# MCH_FPGA_Bank_47_48_67_HP_VHDCI.net
KiCad netlist of a schematic drawn in Altium Designer
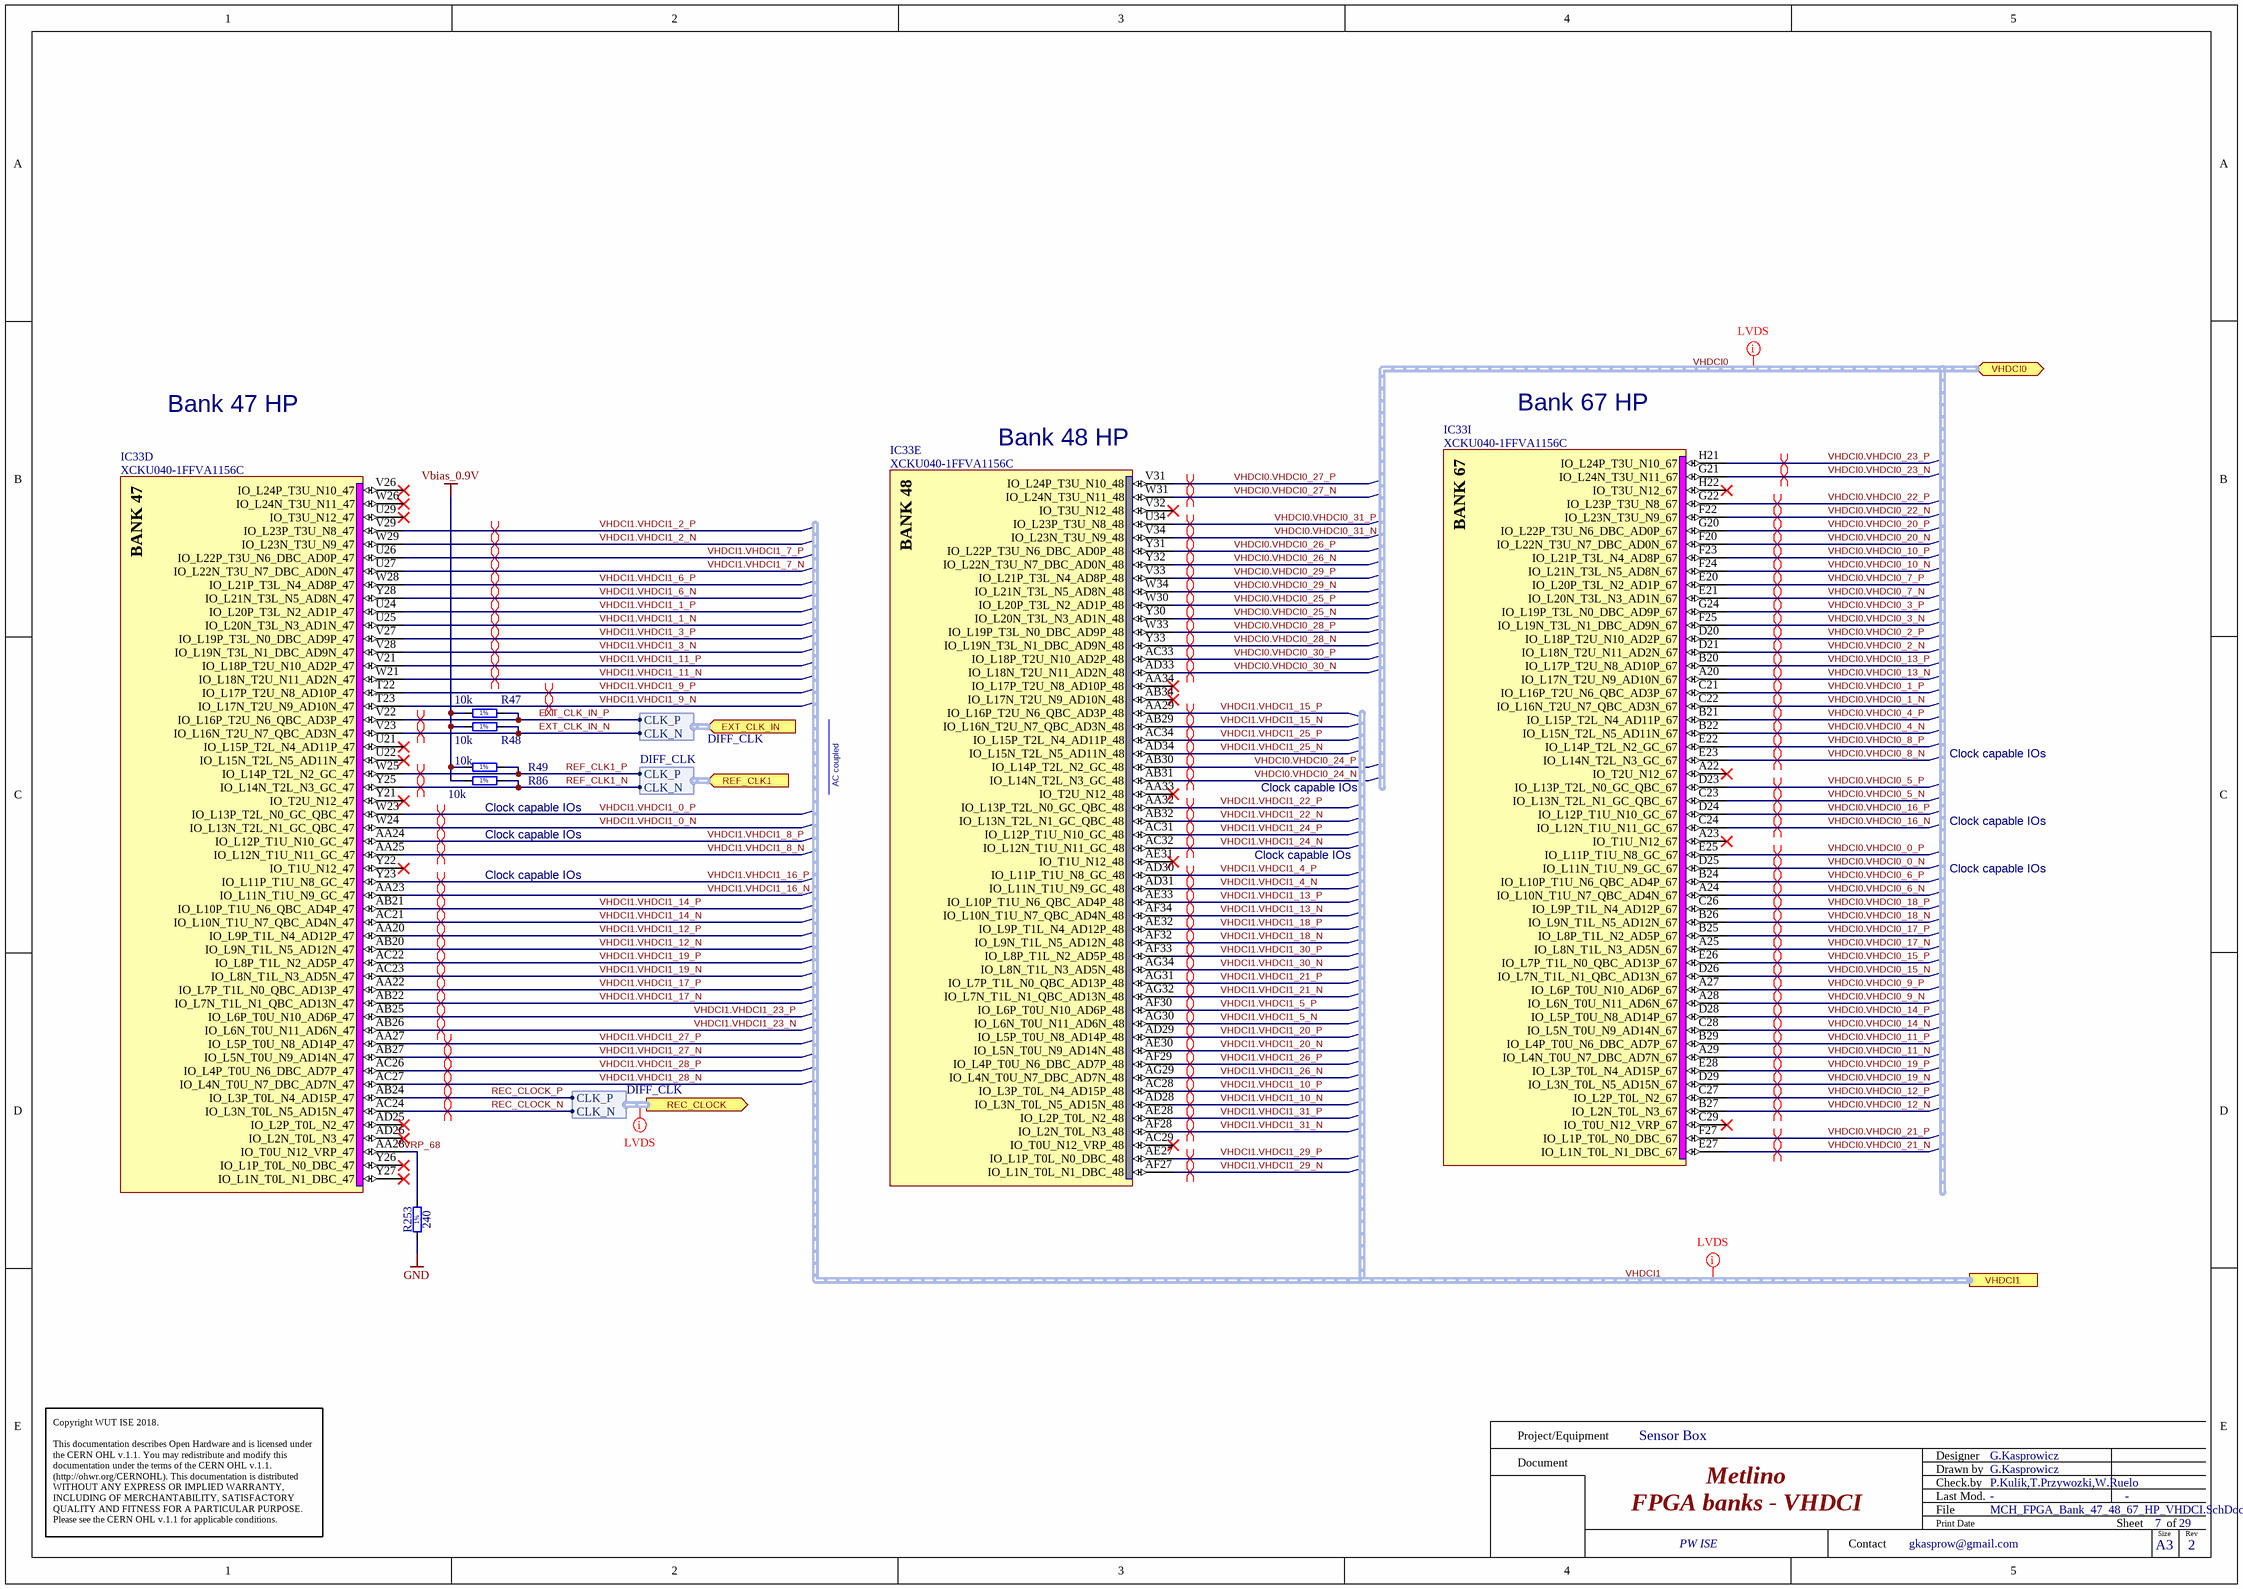
[diagram p0: MCH_FPGA_Bank_47_48_67_HP_VHDCI.SchDoc]

(export (version "E")
  (design (tool "Eeschema 10.0.6"))
  (components
    (comp (ref "IC33")
      (value "XCKU040-1FFVA1156C")
      (footprint "BGA1156C100P34X34_3500X3500X350")
      (description "Kintex UltraScale FPGA, 520 I/O, 530K Cells, 1156-Ball BGA, Speed Grade 1, Commercial Grade")
      (fields (field (name "MANUFACTURER") "XILINX") (field (name "AUTHOR") "CERN DEM CA"))
      (libsource (lib "ICs And Semiconductors") (part "XCKU040-1FFVA1156C"))
    )
    (comp (ref "R47")
      (value "10k")
      (footprint "RESC1005X40N")
      (description "Resistor - 1%")
      (fields
        (field (name "MANUFACTURER PART NUMBER") "R0402_10K_1%_0.0625W_100PPM")
        (field (name "MANUFACTURER") "GENERIC")
        (field (name "AUTHOR") "CERN DEM JLC")
      )
      (libsource (lib "Resistors") (part "Resistor - 1%"))
    )
    (comp (ref "R48")
      (value "10k")
      (footprint "RESC1005X40N")
      (description "Resistor - 1%")
      (fields
        (field (name "MANUFACTURER PART NUMBER") "R0402_10K_1%_0.0625W_100PPM")
        (field (name "MANUFACTURER") "GENERIC")
        (field (name "AUTHOR") "CERN DEM JLC")
      )
      (libsource (lib "Resistors") (part "Resistor - 1%"))
    )
    (comp (ref "R49")
      (value "10k")
      (footprint "RESC1005X40N")
      (description "Resistor - 1%")
      (fields
        (field (name "MANUFACTURER PART NUMBER") "R0402_10K_1%_0.0625W_100PPM")
        (field (name "MANUFACTURER") "GENERIC")
        (field (name "AUTHOR") "CERN DEM JLC")
      )
      (libsource (lib "Resistors") (part "Resistor - 1%"))
    )
    (comp (ref "R86")
      (value "10k")
      (footprint "RESC1005X40N")
      (description "Resistor - 1%")
      (fields
        (field (name "MANUFACTURER PART NUMBER") "R0402_10K_1%_0.0625W_100PPM")
        (field (name "MANUFACTURER") "GENERIC")
        (field (name "AUTHOR") "CERN DEM JLC")
      )
      (libsource (lib "Resistors") (part "Resistor - 1%"))
    )
    (comp (ref "R253")
      (value "240")
      (footprint "RESC1005X40N")
      (description "Resistor - 1%")
      (fields
        (field (name "MANUFACTURER PART NUMBER") "R0402_240R_1%_0.0625W_100PPM")
        (field (name "MANUFACTURER") "GENERIC")
        (field (name "AUTHOR") "CERN DEM JLC")
      )
      (libsource (lib "Resistors") (part "Resistor - 1%"))
    )
  )
  (nets
    (net (code "4") (name "/EXT_CLK_IN_N") (class "Default")
      (node (ref "IC33") (pin "V23") (pinfunction "IO_L16N_T2U_N7_QBC_AD3N_47_V23") (pintype "bidirectional"))
      (node (ref "R48") (pin "2") (pinfunction "2_2") (pintype "passive"))
    )
    (net (code "5") (name "/EXT_CLK_IN_P") (class "Default")
      (node (ref "IC33") (pin "V22") (pinfunction "IO_L16P_T2U_N6_QBC_AD3P_47_V22") (pintype "bidirectional"))
      (node (ref "R47") (pin "2") (pinfunction "2_2") (pintype "passive"))
    )
    (net (code "6") (name "/REC_CLOCK_N") (class "Default")
      (node (ref "IC33") (pin "AC24") (pinfunction "IO_L3N_T0L_N5_AD15N_47_AC24") (pintype "bidirectional"))
    )
    (net (code "7") (name "/REC_CLOCK_P") (class "Default")
      (node (ref "IC33") (pin "AB24") (pinfunction "IO_L3P_T0L_N4_AD15P_47_AB24") (pintype "bidirectional"))
    )
    (net (code "8") (name "/REF_CLK1_N") (class "Default")
      (node (ref "IC33") (pin "Y25") (pinfunction "IO_L14N_T2L_N3_GC_47_Y25") (pintype "bidirectional"))
      (node (ref "R86") (pin "2") (pinfunction "2_2") (pintype "passive"))
    )
    (net (code "9") (name "/REF_CLK1_P") (class "Default")
      (node (ref "IC33") (pin "W25") (pinfunction "IO_L14P_T2L_N2_GC_47_W25") (pintype "bidirectional"))
      (node (ref "R49") (pin "2") (pinfunction "2_2") (pintype "passive"))
    )
    (net (code "10") (name "/VHDCI0.VHDCI0_0_N") (class "Default")
      (node (ref "IC33") (pin "D25") (pinfunction "IO_L11N_T1U_N9_GC_67_D25") (pintype "bidirectional"))
    )
    (net (code "11") (name "/VHDCI0.VHDCI0_0_P") (class "Default")
      (node (ref "IC33") (pin "E25") (pinfunction "IO_L11P_T1U_N8_GC_67_E25") (pintype "bidirectional"))
    )
    (net (code "12") (name "/VHDCI0.VHDCI0_1_N") (class "Default")
      (node (ref "IC33") (pin "C22") (pinfunction "IO_L16N_T2U_N7_QBC_AD3N_67_C22") (pintype "bidirectional"))
    )
    (net (code "13") (name "/VHDCI0.VHDCI0_1_P") (class "Default")
      (node (ref "IC33") (pin "C21") (pinfunction "IO_L16P_T2U_N6_QBC_AD3P_67_C21") (pintype "bidirectional"))
    )
    (net (code "14") (name "/VHDCI0.VHDCI0_2_N") (class "Default")
      (node (ref "IC33") (pin "D21") (pinfunction "IO_L18N_T2U_N11_AD2N_67_D21") (pintype "bidirectional"))
    )
    (net (code "15") (name "/VHDCI0.VHDCI0_2_P") (class "Default")
      (node (ref "IC33") (pin "D20") (pinfunction "IO_L18P_T2U_N10_AD2P_67_D20") (pintype "bidirectional"))
    )
    (net (code "16") (name "/VHDCI0.VHDCI0_3_N") (class "Default")
      (node (ref "IC33") (pin "F25") (pinfunction "IO_L19N_T3L_N1_DBC_AD9N_67_F25") (pintype "bidirectional"))
    )
    (net (code "17") (name "/VHDCI0.VHDCI0_3_P") (class "Default")
      (node (ref "IC33") (pin "G24") (pinfunction "IO_L19P_T3L_N0_DBC_AD9P_67_G24") (pintype "bidirectional"))
    )
    (net (code "18") (name "/VHDCI0.VHDCI0_4_N") (class "Default")
      (node (ref "IC33") (pin "B22") (pinfunction "IO_L15N_T2L_N5_AD11N_67_B22") (pintype "bidirectional"))
    )
    (net (code "19") (name "/VHDCI0.VHDCI0_4_P") (class "Default")
      (node (ref "IC33") (pin "B21") (pinfunction "IO_L15P_T2L_N4_AD11P_67_B21") (pintype "bidirectional"))
    )
    (net (code "20") (name "/VHDCI0.VHDCI0_5_N") (class "Default")
      (node (ref "IC33") (pin "C23") (pinfunction "IO_L13N_T2L_N1_GC_QBC_67_C23") (pintype "bidirectional"))
    )
    (net (code "21") (name "/VHDCI0.VHDCI0_5_P") (class "Default")
      (node (ref "IC33") (pin "D23") (pinfunction "IO_L13P_T2L_N0_GC_QBC_67_D23") (pintype "bidirectional"))
    )
    (net (code "22") (name "/VHDCI0.VHDCI0_6_N") (class "Default")
      (node (ref "IC33") (pin "A24") (pinfunction "IO_L10N_T1U_N7_QBC_AD4N_67_A24") (pintype "bidirectional"))
    )
    (net (code "23") (name "/VHDCI0.VHDCI0_6_P") (class "Default")
      (node (ref "IC33") (pin "B24") (pinfunction "IO_L10P_T1U_N6_QBC_AD4P_67_B24") (pintype "bidirectional"))
    )
    (net (code "24") (name "/VHDCI0.VHDCI0_7_N") (class "Default")
      (node (ref "IC33") (pin "E21") (pinfunction "IO_L20N_T3L_N3_AD1N_67_E21") (pintype "bidirectional"))
    )
    (net (code "25") (name "/VHDCI0.VHDCI0_7_P") (class "Default")
      (node (ref "IC33") (pin "E20") (pinfunction "IO_L20P_T3L_N2_AD1P_67_E20") (pintype "bidirectional"))
    )
    (net (code "26") (name "/VHDCI0.VHDCI0_8_N") (class "Default")
      (node (ref "IC33") (pin "E23") (pinfunction "IO_L14N_T2L_N3_GC_67_E23") (pintype "bidirectional"))
    )
    (net (code "27") (name "/VHDCI0.VHDCI0_8_P") (class "Default")
      (node (ref "IC33") (pin "E22") (pinfunction "IO_L14P_T2L_N2_GC_67_E22") (pintype "bidirectional"))
    )
    (net (code "28") (name "/VHDCI0.VHDCI0_9_N") (class "Default")
      (node (ref "IC33") (pin "A28") (pinfunction "IO_L6N_T0U_N11_AD6N_67_A28") (pintype "bidirectional"))
    )
    (net (code "29") (name "/VHDCI0.VHDCI0_9_P") (class "Default")
      (node (ref "IC33") (pin "A27") (pinfunction "IO_L6P_T0U_N10_AD6P_67_A27") (pintype "bidirectional"))
    )
    (net (code "30") (name "/VHDCI0.VHDCI0_10_N") (class "Default")
      (node (ref "IC33") (pin "F24") (pinfunction "IO_L21N_T3L_N5_AD8N_67_F24") (pintype "bidirectional"))
    )
    (net (code "31") (name "/VHDCI0.VHDCI0_10_P") (class "Default")
      (node (ref "IC33") (pin "F23") (pinfunction "IO_L21P_T3L_N4_AD8P_67_F23") (pintype "bidirectional"))
    )
    (net (code "32") (name "/VHDCI0.VHDCI0_11_N") (class "Default")
      (node (ref "IC33") (pin "A29") (pinfunction "IO_L4N_T0U_N7_DBC_AD7N_67_A29") (pintype "bidirectional"))
    )
    (net (code "33") (name "/VHDCI0.VHDCI0_11_P") (class "Default")
      (node (ref "IC33") (pin "B29") (pinfunction "IO_L4P_T0U_N6_DBC_AD7P_67_B29") (pintype "bidirectional"))
    )
    (net (code "34") (name "/VHDCI0.VHDCI0_12_N") (class "Default")
      (node (ref "IC33") (pin "B27") (pinfunction "IO_L2N_T0L_N3_67_B27") (pintype "bidirectional"))
    )
    (net (code "35") (name "/VHDCI0.VHDCI0_12_P") (class "Default")
      (node (ref "IC33") (pin "C27") (pinfunction "IO_L2P_T0L_N2_67_C27") (pintype "bidirectional"))
    )
    (net (code "36") (name "/VHDCI0.VHDCI0_13_N") (class "Default")
      (node (ref "IC33") (pin "A20") (pinfunction "IO_L17N_T2U_N9_AD10N_67_A20") (pintype "bidirectional"))
    )
    (net (code "37") (name "/VHDCI0.VHDCI0_13_P") (class "Default")
      (node (ref "IC33") (pin "B20") (pinfunction "IO_L17P_T2U_N8_AD10P_67_B20") (pintype "bidirectional"))
    )
    (net (code "38") (name "/VHDCI0.VHDCI0_14_N") (class "Default")
      (node (ref "IC33") (pin "C28") (pinfunction "IO_L5N_T0U_N9_AD14N_67_C28") (pintype "bidirectional"))
    )
    (net (code "39") (name "/VHDCI0.VHDCI0_14_P") (class "Default")
      (node (ref "IC33") (pin "D28") (pinfunction "IO_L5P_T0U_N8_AD14P_67_D28") (pintype "bidirectional"))
    )
    (net (code "40") (name "/VHDCI0.VHDCI0_15_N") (class "Default")
      (node (ref "IC33") (pin "D26") (pinfunction "IO_L7N_T1L_N1_QBC_AD13N_67_D26") (pintype "bidirectional"))
    )
    (net (code "41") (name "/VHDCI0.VHDCI0_15_P") (class "Default")
      (node (ref "IC33") (pin "E26") (pinfunction "IO_L7P_T1L_N0_QBC_AD13P_67_E26") (pintype "bidirectional"))
    )
    (net (code "42") (name "/VHDCI0.VHDCI0_16_N") (class "Default")
      (node (ref "IC33") (pin "C24") (pinfunction "IO_L12N_T1U_N11_GC_67_C24") (pintype "bidirectional"))
    )
    (net (code "43") (name "/VHDCI0.VHDCI0_16_P") (class "Default")
      (node (ref "IC33") (pin "D24") (pinfunction "IO_L12P_T1U_N10_GC_67_D24") (pintype "bidirectional"))
    )
    (net (code "44") (name "/VHDCI0.VHDCI0_17_N") (class "Default")
      (node (ref "IC33") (pin "A25") (pinfunction "IO_L8N_T1L_N3_AD5N_67_A25") (pintype "bidirectional"))
    )
    (net (code "45") (name "/VHDCI0.VHDCI0_17_P") (class "Default")
      (node (ref "IC33") (pin "B25") (pinfunction "IO_L8P_T1L_N2_AD5P_67_B25") (pintype "bidirectional"))
    )
    (net (code "46") (name "/VHDCI0.VHDCI0_18_N") (class "Default")
      (node (ref "IC33") (pin "B26") (pinfunction "IO_L9N_T1L_N5_AD12N_67_B26") (pintype "bidirectional"))
    )
    (net (code "47") (name "/VHDCI0.VHDCI0_18_P") (class "Default")
      (node (ref "IC33") (pin "C26") (pinfunction "IO_L9P_T1L_N4_AD12P_67_C26") (pintype "bidirectional"))
    )
    (net (code "48") (name "/VHDCI0.VHDCI0_19_N") (class "Default")
      (node (ref "IC33") (pin "D29") (pinfunction "IO_L3N_T0L_N5_AD15N_67_D29") (pintype "bidirectional"))
    )
    (net (code "49") (name "/VHDCI0.VHDCI0_19_P") (class "Default")
      (node (ref "IC33") (pin "E28") (pinfunction "IO_L3P_T0L_N4_AD15P_67_E28") (pintype "bidirectional"))
    )
    (net (code "50") (name "/VHDCI0.VHDCI0_20_N") (class "Default")
      (node (ref "IC33") (pin "F20") (pinfunction "IO_L22N_T3U_N7_DBC_AD0N_67_F20") (pintype "bidirectional"))
    )
    (net (code "51") (name "/VHDCI0.VHDCI0_20_P") (class "Default")
      (node (ref "IC33") (pin "G20") (pinfunction "IO_L22P_T3U_N6_DBC_AD0P_67_G20") (pintype "bidirectional"))
    )
    (net (code "52") (name "/VHDCI0.VHDCI0_21_N") (class "Default")
      (node (ref "IC33") (pin "E27") (pinfunction "IO_L1N_T0L_N1_DBC_67_E27") (pintype "bidirectional"))
    )
    (net (code "53") (name "/VHDCI0.VHDCI0_21_P") (class "Default")
      (node (ref "IC33") (pin "F27") (pinfunction "IO_L1P_T0L_N0_DBC_67_F27") (pintype "bidirectional"))
    )
    (net (code "54") (name "/VHDCI0.VHDCI0_22_N") (class "Default")
      (node (ref "IC33") (pin "F22") (pinfunction "IO_L23N_T3U_N9_67_F22") (pintype "bidirectional"))
    )
    (net (code "55") (name "/VHDCI0.VHDCI0_22_P") (class "Default")
      (node (ref "IC33") (pin "G22") (pinfunction "IO_L23P_T3U_N8_67_G22") (pintype "bidirectional"))
    )
    (net (code "56") (name "/VHDCI0.VHDCI0_23_N") (class "Default")
      (node (ref "IC33") (pin "G21") (pinfunction "IO_L24N_T3U_N11_67_G21") (pintype "bidirectional"))
    )
    (net (code "57") (name "/VHDCI0.VHDCI0_23_P") (class "Default")
      (node (ref "IC33") (pin "H21") (pinfunction "IO_L24P_T3U_N10_67_H21") (pintype "bidirectional"))
    )
    (net (code "58") (name "/VHDCI0.VHDCI0_24_N") (class "Default")
      (node (ref "IC33") (pin "AB31") (pinfunction "IO_L14N_T2L_N3_GC_48_AB31") (pintype "bidirectional"))
    )
    (net (code "59") (name "/VHDCI0.VHDCI0_24_P") (class "Default")
      (node (ref "IC33") (pin "AB30") (pinfunction "IO_L14P_T2L_N2_GC_48_AB30") (pintype "bidirectional"))
    )
    (net (code "60") (name "/VHDCI0.VHDCI0_25_N") (class "Default")
      (node (ref "IC33") (pin "Y30") (pinfunction "IO_L20N_T3L_N3_AD1N_48_Y30") (pintype "bidirectional"))
    )
    (net (code "61") (name "/VHDCI0.VHDCI0_25_P") (class "Default")
      (node (ref "IC33") (pin "W30") (pinfunction "IO_L20P_T3L_N2_AD1P_48_W30") (pintype "bidirectional"))
    )
    (net (code "62") (name "/VHDCI0.VHDCI0_26_N") (class "Default")
      (node (ref "IC33") (pin "Y32") (pinfunction "IO_L22N_T3U_N7_DBC_AD0N_48_Y32") (pintype "bidirectional"))
    )
    (net (code "63") (name "/VHDCI0.VHDCI0_26_P") (class "Default")
      (node (ref "IC33") (pin "Y31") (pinfunction "IO_L22P_T3U_N6_DBC_AD0P_48_Y31") (pintype "bidirectional"))
    )
    (net (code "64") (name "/VHDCI0.VHDCI0_27_N") (class "Default")
      (node (ref "IC33") (pin "W31") (pinfunction "IO_L24N_T3U_N11_48_W31") (pintype "bidirectional"))
    )
    (net (code "65") (name "/VHDCI0.VHDCI0_27_P") (class "Default")
      (node (ref "IC33") (pin "V31") (pinfunction "IO_L24P_T3U_N10_48_V31") (pintype "bidirectional"))
    )
    (net (code "66") (name "/VHDCI0.VHDCI0_28_N") (class "Default")
      (node (ref "IC33") (pin "Y33") (pinfunction "IO_L19N_T3L_N1_DBC_AD9N_48_Y33") (pintype "bidirectional"))
    )
    (net (code "67") (name "/VHDCI0.VHDCI0_28_P") (class "Default")
      (node (ref "IC33") (pin "W33") (pinfunction "IO_L19P_T3L_N0_DBC_AD9P_48_W33") (pintype "bidirectional"))
    )
    (net (code "68") (name "/VHDCI0.VHDCI0_29_N") (class "Default")
      (node (ref "IC33") (pin "W34") (pinfunction "IO_L21N_T3L_N5_AD8N_48_W34") (pintype "bidirectional"))
    )
    (net (code "69") (name "/VHDCI0.VHDCI0_29_P") (class "Default")
      (node (ref "IC33") (pin "V33") (pinfunction "IO_L21P_T3L_N4_AD8P_48_V33") (pintype "bidirectional"))
    )
    (net (code "70") (name "/VHDCI0.VHDCI0_30_N") (class "Default")
      (node (ref "IC33") (pin "AD33") (pinfunction "IO_L18N_T2U_N11_AD2N_48_AD33") (pintype "bidirectional"))
    )
    (net (code "71") (name "/VHDCI0.VHDCI0_30_P") (class "Default")
      (node (ref "IC33") (pin "AC33") (pinfunction "IO_L18P_T2U_N10_AD2P_48_AC33") (pintype "bidirectional"))
    )
    (net (code "72") (name "/VHDCI0.VHDCI0_31_N") (class "Default")
      (node (ref "IC33") (pin "V34") (pinfunction "IO_L23N_T3U_N9_48_V34") (pintype "bidirectional"))
    )
    (net (code "73") (name "/VHDCI0.VHDCI0_31_P") (class "Default")
      (node (ref "IC33") (pin "U34") (pinfunction "IO_L23P_T3U_N8_48_U34") (pintype "bidirectional"))
    )
    (net (code "74") (name "/VHDCI1.VHDCI1_0_N") (class "Default")
      (node (ref "IC33") (pin "W24") (pinfunction "IO_L13N_T2L_N1_GC_QBC_47_W24") (pintype "bidirectional"))
    )
    (net (code "75") (name "/VHDCI1.VHDCI1_0_P") (class "Default")
      (node (ref "IC33") (pin "W23") (pinfunction "IO_L13P_T2L_N0_GC_QBC_47_W23") (pintype "bidirectional"))
    )
    (net (code "76") (name "/VHDCI1.VHDCI1_1_N") (class "Default")
      (node (ref "IC33") (pin "U25") (pinfunction "IO_L20N_T3L_N3_AD1N_47_U25") (pintype "bidirectional"))
    )
    (net (code "77") (name "/VHDCI1.VHDCI1_1_P") (class "Default")
      (node (ref "IC33") (pin "U24") (pinfunction "IO_L20P_T3L_N2_AD1P_47_U24") (pintype "bidirectional"))
    )
    (net (code "78") (name "/VHDCI1.VHDCI1_2_N") (class "Default")
      (node (ref "IC33") (pin "W29") (pinfunction "IO_L23N_T3U_N9_47_W29") (pintype "bidirectional"))
    )
    (net (code "79") (name "/VHDCI1.VHDCI1_2_P") (class "Default")
      (node (ref "IC33") (pin "V29") (pinfunction "IO_L23P_T3U_N8_47_V29") (pintype "bidirectional"))
    )
    (net (code "80") (name "/VHDCI1.VHDCI1_3_N") (class "Default")
      (node (ref "IC33") (pin "V28") (pinfunction "IO_L19N_T3L_N1_DBC_AD9N_47_V28") (pintype "bidirectional"))
    )
    (net (code "81") (name "/VHDCI1.VHDCI1_3_P") (class "Default")
      (node (ref "IC33") (pin "V27") (pinfunction "IO_L19P_T3L_N0_DBC_AD9P_47_V27") (pintype "bidirectional"))
    )
    (net (code "82") (name "/VHDCI1.VHDCI1_4_N") (class "Default")
      (node (ref "IC33") (pin "AD31") (pinfunction "IO_L11N_T1U_N9_GC_48_AD31") (pintype "bidirectional"))
    )
    (net (code "83") (name "/VHDCI1.VHDCI1_4_P") (class "Default")
      (node (ref "IC33") (pin "AD30") (pinfunction "IO_L11P_T1U_N8_GC_48_AD30") (pintype "bidirectional"))
    )
    (net (code "84") (name "/VHDCI1.VHDCI1_5_N") (class "Default")
      (node (ref "IC33") (pin "AG30") (pinfunction "IO_L6N_T0U_N11_AD6N_48_AG30") (pintype "bidirectional"))
    )
    (net (code "85") (name "/VHDCI1.VHDCI1_5_P") (class "Default")
      (node (ref "IC33") (pin "AF30") (pinfunction "IO_L6P_T0U_N10_AD6P_48_AF30") (pintype "bidirectional"))
    )
    (net (code "86") (name "/VHDCI1.VHDCI1_6_N") (class "Default")
      (node (ref "IC33") (pin "Y28") (pinfunction "IO_L21N_T3L_N5_AD8N_47_Y28") (pintype "bidirectional"))
    )
    (net (code "87") (name "/VHDCI1.VHDCI1_6_P") (class "Default")
      (node (ref "IC33") (pin "W28") (pinfunction "IO_L21P_T3L_N4_AD8P_47_W28") (pintype "bidirectional"))
    )
    (net (code "88") (name "/VHDCI1.VHDCI1_7_N") (class "Default")
      (node (ref "IC33") (pin "U27") (pinfunction "IO_L22N_T3U_N7_DBC_AD0N_47_U27") (pintype "bidirectional"))
    )
    (net (code "89") (name "/VHDCI1.VHDCI1_7_P") (class "Default")
      (node (ref "IC33") (pin "U26") (pinfunction "IO_L22P_T3U_N6_DBC_AD0P_47_U26") (pintype "bidirectional"))
    )
    (net (code "90") (name "/VHDCI1.VHDCI1_8_N") (class "Default")
      (node (ref "IC33") (pin "AA25") (pinfunction "IO_L12N_T1U_N11_GC_47_AA25") (pintype "bidirectional"))
    )
    (net (code "91") (name "/VHDCI1.VHDCI1_8_P") (class "Default")
      (node (ref "IC33") (pin "AA24") (pinfunction "IO_L12P_T1U_N10_GC_47_AA24") (pintype "bidirectional"))
    )
    (net (code "92") (name "/VHDCI1.VHDCI1_9_N") (class "Default")
      (node (ref "IC33") (pin "T23") (pinfunction "IO_L17N_T2U_N9_AD10N_47_T23") (pintype "bidirectional"))
    )
    (net (code "93") (name "/VHDCI1.VHDCI1_9_P") (class "Default")
      (node (ref "IC33") (pin "T22") (pinfunction "IO_L17P_T2U_N8_AD10P_47_T22") (pintype "bidirectional"))
    )
    (net (code "94") (name "/VHDCI1.VHDCI1_10_N") (class "Default")
      (node (ref "IC33") (pin "AD28") (pinfunction "IO_L3N_T0L_N5_AD15N_48_AD28") (pintype "bidirectional"))
    )
    (net (code "95") (name "/VHDCI1.VHDCI1_10_P") (class "Default")
      (node (ref "IC33") (pin "AC28") (pinfunction "IO_L3P_T0L_N4_AD15P_48_AC28") (pintype "bidirectional"))
    )
    (net (code "96") (name "/VHDCI1.VHDCI1_11_N") (class "Default")
      (node (ref "IC33") (pin "W21") (pinfunction "IO_L18N_T2U_N11_AD2N_47_W21") (pintype "bidirectional"))
    )
    (net (code "97") (name "/VHDCI1.VHDCI1_11_P") (class "Default")
      (node (ref "IC33") (pin "V21") (pinfunction "IO_L18P_T2U_N10_AD2P_47_V21") (pintype "bidirectional"))
    )
    (net (code "98") (name "/VHDCI1.VHDCI1_12_N") (class "Default")
      (node (ref "IC33") (pin "AB20") (pinfunction "IO_L9N_T1L_N5_AD12N_47_AB20") (pintype "bidirectional"))
    )
    (net (code "99") (name "/VHDCI1.VHDCI1_12_P") (class "Default")
      (node (ref "IC33") (pin "AA20") (pinfunction "IO_L9P_T1L_N4_AD12P_47_AA20") (pintype "bidirectional"))
    )
    (net (code "100") (name "/VHDCI1.VHDCI1_13_N") (class "Default")
      (node (ref "IC33") (pin "AF34") (pinfunction "IO_L10N_T1U_N7_QBC_AD4N_48_AF34") (pintype "bidirectional"))
    )
    (net (code "101") (name "/VHDCI1.VHDCI1_13_P") (class "Default")
      (node (ref "IC33") (pin "AE33") (pinfunction "IO_L10P_T1U_N6_QBC_AD4P_48_AE33") (pintype "bidirectional"))
    )
    (net (code "102") (name "/VHDCI1.VHDCI1_14_N") (class "Default")
      (node (ref "IC33") (pin "AC21") (pinfunction "IO_L10N_T1U_N7_QBC_AD4N_47_AC21") (pintype "bidirectional"))
    )
    (net (code "103") (name "/VHDCI1.VHDCI1_14_P") (class "Default")
      (node (ref "IC33") (pin "AB21") (pinfunction "IO_L10P_T1U_N6_QBC_AD4P_47_AB21") (pintype "bidirectional"))
    )
    (net (code "104") (name "/VHDCI1.VHDCI1_15_N") (class "Default")
      (node (ref "IC33") (pin "AB29") (pinfunction "IO_L16N_T2U_N7_QBC_AD3N_48_AB29") (pintype "bidirectional"))
    )
    (net (code "105") (name "/VHDCI1.VHDCI1_15_P") (class "Default")
      (node (ref "IC33") (pin "AA29") (pinfunction "IO_L16P_T2U_N6_QBC_AD3P_48_AA29") (pintype "bidirectional"))
    )
    (net (code "106") (name "/VHDCI1.VHDCI1_16_N") (class "Default")
      (node (ref "IC33") (pin "AA23") (pinfunction "IO_L11N_T1U_N9_GC_47_AA23") (pintype "bidirectional"))
    )
    (net (code "107") (name "/VHDCI1.VHDCI1_16_P") (class "Default")
      (node (ref "IC33") (pin "Y23") (pinfunction "IO_L11P_T1U_N8_GC_47_Y23") (pintype "bidirectional"))
    )
    (net (code "108") (name "/VHDCI1.VHDCI1_17_N") (class "Default")
      (node (ref "IC33") (pin "AB22") (pinfunction "IO_L7N_T1L_N1_QBC_AD13N_47_AB22") (pintype "bidirectional"))
    )
    (net (code "109") (name "/VHDCI1.VHDCI1_17_P") (class "Default")
      (node (ref "IC33") (pin "AA22") (pinfunction "IO_L7P_T1L_N0_QBC_AD13P_47_AA22") (pintype "bidirectional"))
    )
    (net (code "110") (name "/VHDCI1.VHDCI1_18_N") (class "Default")
      (node (ref "IC33") (pin "AF32") (pinfunction "IO_L9N_T1L_N5_AD12N_48_AF32") (pintype "bidirectional"))
    )
    (net (code "111") (name "/VHDCI1.VHDCI1_18_P") (class "Default")
      (node (ref "IC33") (pin "AE32") (pinfunction "IO_L9P_T1L_N4_AD12P_48_AE32") (pintype "bidirectional"))
    )
    (net (code "112") (name "/VHDCI1.VHDCI1_19_N") (class "Default")
      (node (ref "IC33") (pin "AC23") (pinfunction "IO_L8N_T1L_N3_AD5N_47_AC23") (pintype "bidirectional"))
    )
    (net (code "113") (name "/VHDCI1.VHDCI1_19_P") (class "Default")
      (node (ref "IC33") (pin "AC22") (pinfunction "IO_L8P_T1L_N2_AD5P_47_AC22") (pintype "bidirectional"))
    )
    (net (code "114") (name "/VHDCI1.VHDCI1_20_N") (class "Default")
      (node (ref "IC33") (pin "AE30") (pinfunction "IO_L5N_T0U_N9_AD14N_48_AE30") (pintype "bidirectional"))
    )
    (net (code "115") (name "/VHDCI1.VHDCI1_20_P") (class "Default")
      (node (ref "IC33") (pin "AD29") (pinfunction "IO_L5P_T0U_N8_AD14P_48_AD29") (pintype "bidirectional"))
    )
    (net (code "116") (name "/VHDCI1.VHDCI1_21_N") (class "Default")
      (node (ref "IC33") (pin "AG32") (pinfunction "IO_L7N_T1L_N1_QBC_AD13N_48_AG32") (pintype "bidirectional"))
    )
    (net (code "117") (name "/VHDCI1.VHDCI1_21_P") (class "Default")
      (node (ref "IC33") (pin "AG31") (pinfunction "IO_L7P_T1L_N0_QBC_AD13P_48_AG31") (pintype "bidirectional"))
    )
    (net (code "118") (name "/VHDCI1.VHDCI1_22_N") (class "Default")
      (node (ref "IC33") (pin "AB32") (pinfunction "IO_L13N_T2L_N1_GC_QBC_48_AB32") (pintype "bidirectional"))
    )
    (net (code "119") (name "/VHDCI1.VHDCI1_22_P") (class "Default")
      (node (ref "IC33") (pin "AA32") (pinfunction "IO_L13P_T2L_N0_GC_QBC_48_AA32") (pintype "bidirectional"))
    )
    (net (code "120") (name "/VHDCI1.VHDCI1_23_N") (class "Default")
      (node (ref "IC33") (pin "AB26") (pinfunction "IO_L6N_T0U_N11_AD6N_47_AB26") (pintype "bidirectional"))
    )
    (net (code "121") (name "/VHDCI1.VHDCI1_23_P") (class "Default")
      (node (ref "IC33") (pin "AB25") (pinfunction "IO_L6P_T0U_N10_AD6P_47_AB25") (pintype "bidirectional"))
    )
    (net (code "122") (name "/VHDCI1.VHDCI1_24_N") (class "Default")
      (node (ref "IC33") (pin "AC32") (pinfunction "IO_L12N_T1U_N11_GC_48_AC32") (pintype "bidirectional"))
    )
    (net (code "123") (name "/VHDCI1.VHDCI1_24_P") (class "Default")
      (node (ref "IC33") (pin "AC31") (pinfunction "IO_L12P_T1U_N10_GC_48_AC31") (pintype "bidirectional"))
    )
    (net (code "124") (name "/VHDCI1.VHDCI1_25_N") (class "Default")
      (node (ref "IC33") (pin "AD34") (pinfunction "IO_L15N_T2L_N5_AD11N_48_AD34") (pintype "bidirectional"))
    )
    (net (code "125") (name "/VHDCI1.VHDCI1_25_P") (class "Default")
      (node (ref "IC33") (pin "AC34") (pinfunction "IO_L15P_T2L_N4_AD11P_48_AC34") (pintype "bidirectional"))
    )
    (net (code "126") (name "/VHDCI1.VHDCI1_26_N") (class "Default")
      (node (ref "IC33") (pin "AG29") (pinfunction "IO_L4N_T0U_N7_DBC_AD7N_48_AG29") (pintype "bidirectional"))
    )
    (net (code "127") (name "/VHDCI1.VHDCI1_26_P") (class "Default")
      (node (ref "IC33") (pin "AF29") (pinfunction "IO_L4P_T0U_N6_DBC_AD7P_48_AF29") (pintype "bidirectional"))
    )
    (net (code "128") (name "/VHDCI1.VHDCI1_27_N") (class "Default")
      (node (ref "IC33") (pin "AB27") (pinfunction "IO_L5N_T0U_N9_AD14N_47_AB27") (pintype "bidirectional"))
    )
    (net (code "129") (name "/VHDCI1.VHDCI1_27_P") (class "Default")
      (node (ref "IC33") (pin "AA27") (pinfunction "IO_L5P_T0U_N8_AD14P_47_AA27") (pintype "bidirectional"))
    )
    (net (code "130") (name "/VHDCI1.VHDCI1_28_N") (class "Default")
      (node (ref "IC33") (pin "AC27") (pinfunction "IO_L4N_T0U_N7_DBC_AD7N_47_AC27") (pintype "bidirectional"))
    )
    (net (code "131") (name "/VHDCI1.VHDCI1_28_P") (class "Default")
      (node (ref "IC33") (pin "AC26") (pinfunction "IO_L4P_T0U_N6_DBC_AD7P_47_AC26") (pintype "bidirectional"))
    )
    (net (code "132") (name "/VHDCI1.VHDCI1_29_N") (class "Default")
      (node (ref "IC33") (pin "AF27") (pinfunction "IO_L1N_T0L_N1_DBC_48_AF27") (pintype "bidirectional"))
    )
    (net (code "133") (name "/VHDCI1.VHDCI1_29_P") (class "Default")
      (node (ref "IC33") (pin "AE27") (pinfunction "IO_L1P_T0L_N0_DBC_48_AE27") (pintype "bidirectional"))
    )
    (net (code "134") (name "/VHDCI1.VHDCI1_30_N") (class "Default")
      (node (ref "IC33") (pin "AG34") (pinfunction "IO_L8N_T1L_N3_AD5N_48_AG34") (pintype "bidirectional"))
    )
    (net (code "135") (name "/VHDCI1.VHDCI1_30_P") (class "Default")
      (node (ref "IC33") (pin "AF33") (pinfunction "IO_L8P_T1L_N2_AD5P_48_AF33") (pintype "bidirectional"))
    )
    (net (code "136") (name "/VHDCI1.VHDCI1_31_N") (class "Default")
      (node (ref "IC33") (pin "AF28") (pinfunction "IO_L2N_T0L_N3_48_AF28") (pintype "bidirectional"))
    )
    (net (code "137") (name "/VHDCI1.VHDCI1_31_P") (class "Default")
      (node (ref "IC33") (pin "AE28") (pinfunction "IO_L2P_T0L_N2_48_AE28") (pintype "bidirectional"))
    )
    (net (code "138") (name "/VRP_68") (class "Default")
      (node (ref "IC33") (pin "AA28") (pinfunction "IO_T0U_N12_VRP_47_AA28") (pintype "bidirectional"))
      (node (ref "R253") (pin "2") (pinfunction "2_2") (pintype "passive"))
    )
    (net (code "142") (name "GND") (class "Default")
      (node (ref "R253") (pin "1") (pinfunction "1_1") (pintype "passive"))
    )
    (net (code "143") (name "Vbias_0.9V") (class "Default")
      (node (ref "R47") (pin "1") (pinfunction "1_1") (pintype "passive"))
      (node (ref "R48") (pin "1") (pinfunction "1_1") (pintype "passive"))
      (node (ref "R49") (pin "1") (pinfunction "1_1") (pintype "passive"))
      (node (ref "R86") (pin "1") (pinfunction "1_1") (pintype "passive"))
    )
    (net (code "144") (name "unconnected-(IC33D-IO_L1N_T0L_N1_DBC_47-PadY27)") (class "Default")
      (node (ref "IC33") (pin "Y27") (pinfunction "IO_L1N_T0L_N1_DBC_47_Y27") (pintype "bidirectional+no_connect"))
    )
    (net (code "145") (name "unconnected-(IC33D-IO_L1P_T0L_N0_DBC_47-PadY26)") (class "Default")
      (node (ref "IC33") (pin "Y26") (pinfunction "IO_L1P_T0L_N0_DBC_47_Y26") (pintype "bidirectional+no_connect"))
    )
    (net (code "146") (name "unconnected-(IC33D-IO_L2N_T0L_N3_47-PadAD26)") (class "Default")
      (node (ref "IC33") (pin "AD26") (pinfunction "IO_L2N_T0L_N3_47_AD26") (pintype "bidirectional+no_connect"))
    )
    (net (code "147") (name "unconnected-(IC33D-IO_L2P_T0L_N2_47-PadAD25)") (class "Default")
      (node (ref "IC33") (pin "AD25") (pinfunction "IO_L2P_T0L_N2_47_AD25") (pintype "bidirectional+no_connect"))
    )
    (net (code "148") (name "unconnected-(IC33D-IO_L15N_T2L_N5_AD11N_47-PadU22)") (class "Default")
      (node (ref "IC33") (pin "U22") (pinfunction "IO_L15N_T2L_N5_AD11N_47_U22") (pintype "bidirectional+no_connect"))
    )
    (net (code "149") (name "unconnected-(IC33D-IO_L15P_T2L_N4_AD11P_47-PadU21)") (class "Default")
      (node (ref "IC33") (pin "U21") (pinfunction "IO_L15P_T2L_N4_AD11P_47_U21") (pintype "bidirectional+no_connect"))
    )
    (net (code "150") (name "unconnected-(IC33D-IO_L24N_T3U_N11_47-PadW26)") (class "Default")
      (node (ref "IC33") (pin "W26") (pinfunction "IO_L24N_T3U_N11_47_W26") (pintype "bidirectional+no_connect"))
    )
    (net (code "151") (name "unconnected-(IC33D-IO_L24P_T3U_N10_47-PadV26)") (class "Default")
      (node (ref "IC33") (pin "V26") (pinfunction "IO_L24P_T3U_N10_47_V26") (pintype "bidirectional+no_connect"))
    )
    (net (code "152") (name "unconnected-(IC33D-IO_T1U_N12_47-PadY22)") (class "Default")
      (node (ref "IC33") (pin "Y22") (pinfunction "IO_T1U_N12_47_Y22") (pintype "bidirectional+no_connect"))
    )
    (net (code "153") (name "unconnected-(IC33D-IO_T2U_N12_47-PadY21)") (class "Default")
      (node (ref "IC33") (pin "Y21") (pinfunction "IO_T2U_N12_47_Y21") (pintype "bidirectional+no_connect"))
    )
    (net (code "154") (name "unconnected-(IC33D-IO_T3U_N12_47-PadU29)") (class "Default")
      (node (ref "IC33") (pin "U29") (pinfunction "IO_T3U_N12_47_U29") (pintype "bidirectional+no_connect"))
    )
    (net (code "155") (name "unconnected-(IC33E-IO_L17N_T2U_N9_AD10N_48-PadAB34)") (class "Default")
      (node (ref "IC33") (pin "AB34") (pinfunction "IO_L17N_T2U_N9_AD10N_48_AB34") (pintype "bidirectional+no_connect"))
    )
    (net (code "156") (name "unconnected-(IC33E-IO_L17P_T2U_N8_AD10P_48-PadAA34)") (class "Default")
      (node (ref "IC33") (pin "AA34") (pinfunction "IO_L17P_T2U_N8_AD10P_48_AA34") (pintype "bidirectional+no_connect"))
    )
    (net (code "157") (name "unconnected-(IC33E-IO_T0U_N12_VRP_48-PadAC29)") (class "Default")
      (node (ref "IC33") (pin "AC29") (pinfunction "IO_T0U_N12_VRP_48_AC29") (pintype "bidirectional+no_connect"))
    )
    (net (code "158") (name "unconnected-(IC33E-IO_T1U_N12_48-PadAE31)") (class "Default")
      (node (ref "IC33") (pin "AE31") (pinfunction "IO_T1U_N12_48_AE31") (pintype "bidirectional+no_connect"))
    )
    (net (code "159") (name "unconnected-(IC33E-IO_T2U_N12_48-PadAA33)") (class "Default")
      (node (ref "IC33") (pin "AA33") (pinfunction "IO_T2U_N12_48_AA33") (pintype "bidirectional+no_connect"))
    )
    (net (code "160") (name "unconnected-(IC33E-IO_T3U_N12_48-PadV32)") (class "Default")
      (node (ref "IC33") (pin "V32") (pinfunction "IO_T3U_N12_48_V32") (pintype "bidirectional+no_connect"))
    )
    (net (code "161") (name "unconnected-(IC33I-IO_T0U_N12_VRP_67-PadC29)") (class "Default")
      (node (ref "IC33") (pin "C29") (pinfunction "IO_T0U_N12_VRP_67_C29") (pintype "bidirectional+no_connect"))
    )
    (net (code "162") (name "unconnected-(IC33I-IO_T1U_N12_67-PadA23)") (class "Default")
      (node (ref "IC33") (pin "A23") (pinfunction "IO_T1U_N12_67_A23") (pintype "bidirectional+no_connect"))
    )
    (net (code "163") (name "unconnected-(IC33I-IO_T2U_N12_67-PadA22)") (class "Default")
      (node (ref "IC33") (pin "A22") (pinfunction "IO_T2U_N12_67_A22") (pintype "bidirectional+no_connect"))
    )
    (net (code "164") (name "unconnected-(IC33I-IO_T3U_N12_67-PadH22)") (class "Default")
      (node (ref "IC33") (pin "H22") (pinfunction "IO_T3U_N12_67_H22") (pintype "bidirectional+no_connect"))
    )
  )
)
